# CAN_Star.net
KiCad netlist of a schematic drawn in EAGLE
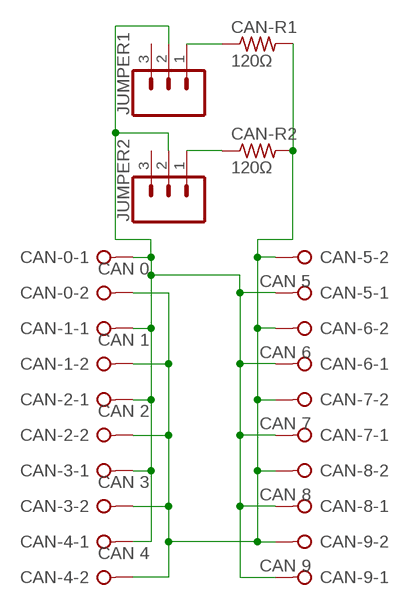
[diagram p0: schematic, sheet 1]

(export (version "E")
  (design (tool "Eeschema 10.0.6"))
  (components
    (comp (ref "CAN-0")
      (value "CAN 0")
      (footprint "eagle-import:W237-132")
      (libsource (lib "eagle-import") (part "W237-02P"))
    )
    (comp (ref "CAN-1")
      (value "CAN 1")
      (footprint "eagle-import:W237-132")
      (libsource (lib "eagle-import") (part "W237-02P"))
    )
    (comp (ref "CAN-2")
      (value "CAN 2")
      (footprint "eagle-import:W237-132")
      (libsource (lib "eagle-import") (part "W237-02P"))
    )
    (comp (ref "CAN-3")
      (value "CAN 3")
      (footprint "eagle-import:W237-132")
      (libsource (lib "eagle-import") (part "W237-02P"))
    )
    (comp (ref "CAN-4")
      (value "CAN 4")
      (footprint "eagle-import:W237-132")
      (libsource (lib "eagle-import") (part "W237-02P"))
    )
    (comp (ref "CAN-5")
      (value "CAN 5")
      (footprint "eagle-import:W237-132")
      (libsource (lib "eagle-import") (part "W237-02P"))
    )
    (comp (ref "CAN-6")
      (value "CAN 6")
      (footprint "eagle-import:W237-132")
      (libsource (lib "eagle-import") (part "W237-02P"))
    )
    (comp (ref "CAN-7")
      (value "CAN 7")
      (footprint "eagle-import:W237-132")
      (libsource (lib "eagle-import") (part "W237-02P"))
    )
    (comp (ref "CAN-8")
      (value "CAN 8")
      (footprint "eagle-import:W237-132")
      (libsource (lib "eagle-import") (part "W237-02P"))
    )
    (comp (ref "CAN-9")
      (value "CAN 9")
      (footprint "eagle-import:W237-132")
      (libsource (lib "eagle-import") (part "W237-02P"))
    )
    (comp (ref "CAN-R1")
      (value "120Ω")
      (footprint "eagle-import:0207_10")
      (libsource (lib "eagle-import") (part "R-US_0207/10"))
    )
    (comp (ref "CAN-R2")
      (value "120Ω")
      (footprint "eagle-import:0207_10")
      (libsource (lib "eagle-import") (part "R-US_0207/10"))
    )
    (comp (ref "JUMPER1")
      (value "CONN_03")
      (footprint "eagle-import:1X03")
      (libsource (lib "eagle-import") (part "CONN_03"))
    )
    (comp (ref "JUMPER2")
      (value "CONN_03")
      (footprint "eagle-import:1X03")
      (libsource (lib "eagle-import") (part "CONN_03"))
    )
  )
  (nets
    (net (code "1") (name "Net-(CAN-0A-KL)") (class "Default")
      (node (ref "CAN-0") (pin "1") (pinfunction "KL_1") (pintype "passive"))
      (node (ref "CAN-1") (pin "1") (pinfunction "KL_1") (pintype "passive"))
      (node (ref "CAN-2") (pin "1") (pinfunction "KL_1") (pintype "passive"))
      (node (ref "CAN-3") (pin "1") (pinfunction "KL_1") (pintype "passive"))
      (node (ref "CAN-4") (pin "1") (pinfunction "KL_1") (pintype "passive"))
      (node (ref "CAN-5") (pin "1") (pinfunction "KL_1") (pintype "passive"))
      (node (ref "CAN-6") (pin "1") (pinfunction "KL_1") (pintype "passive"))
      (node (ref "CAN-7") (pin "1") (pinfunction "KL_1") (pintype "passive"))
      (node (ref "CAN-8") (pin "1") (pinfunction "KL_1") (pintype "passive"))
      (node (ref "CAN-9") (pin "1") (pinfunction "KL_1") (pintype "passive"))
      (node (ref "JUMPER1") (pin "2") (pinfunction "2_2") (pintype "passive"))
      (node (ref "JUMPER2") (pin "2") (pinfunction "2_2") (pintype "passive"))
    )
    (net (code "2") (name "Net-(CAN-0B-KL)") (class "Default")
      (node (ref "CAN-0") (pin "2") (pinfunction "KL_2") (pintype "passive"))
      (node (ref "CAN-1") (pin "2") (pinfunction "KL_2") (pintype "passive"))
      (node (ref "CAN-2") (pin "2") (pinfunction "KL_2") (pintype "passive"))
      (node (ref "CAN-3") (pin "2") (pinfunction "KL_2") (pintype "passive"))
      (node (ref "CAN-4") (pin "2") (pinfunction "KL_2") (pintype "passive"))
      (node (ref "CAN-5") (pin "2") (pinfunction "KL_2") (pintype "passive"))
      (node (ref "CAN-6") (pin "2") (pinfunction "KL_2") (pintype "passive"))
      (node (ref "CAN-7") (pin "2") (pinfunction "KL_2") (pintype "passive"))
      (node (ref "CAN-8") (pin "2") (pinfunction "KL_2") (pintype "passive"))
      (node (ref "CAN-9") (pin "2") (pinfunction "KL_2") (pintype "passive"))
      (node (ref "CAN-R1") (pin "2") (pinfunction "2_2") (pintype "passive"))
      (node (ref "CAN-R2") (pin "2") (pinfunction "2_2") (pintype "passive"))
    )
    (net (code "3") (name "Net-(CAN-R1-Pad1)") (class "Default")
      (node (ref "CAN-R1") (pin "1") (pinfunction "1_1") (pintype "passive"))
      (node (ref "JUMPER1") (pin "1") (pinfunction "1_1") (pintype "passive"))
    )
    (net (code "4") (name "Net-(CAN-R2-Pad1)") (class "Default")
      (node (ref "CAN-R2") (pin "1") (pinfunction "1_1") (pintype "passive"))
      (node (ref "JUMPER2") (pin "1") (pinfunction "1_1") (pintype "passive"))
    )
    (net (code "5") (name "unconnected-(JUMPER1-Pad3)") (class "Default")
      (node (ref "JUMPER1") (pin "3") (pinfunction "3_3") (pintype "passive"))
    )
    (net (code "6") (name "unconnected-(JUMPER2-Pad3)") (class "Default")
      (node (ref "JUMPER2") (pin "3") (pinfunction "3_3") (pintype "passive"))
    )
  )
)
